# Connectors.net
KiCad netlist of a schematic drawn in Altium Designer
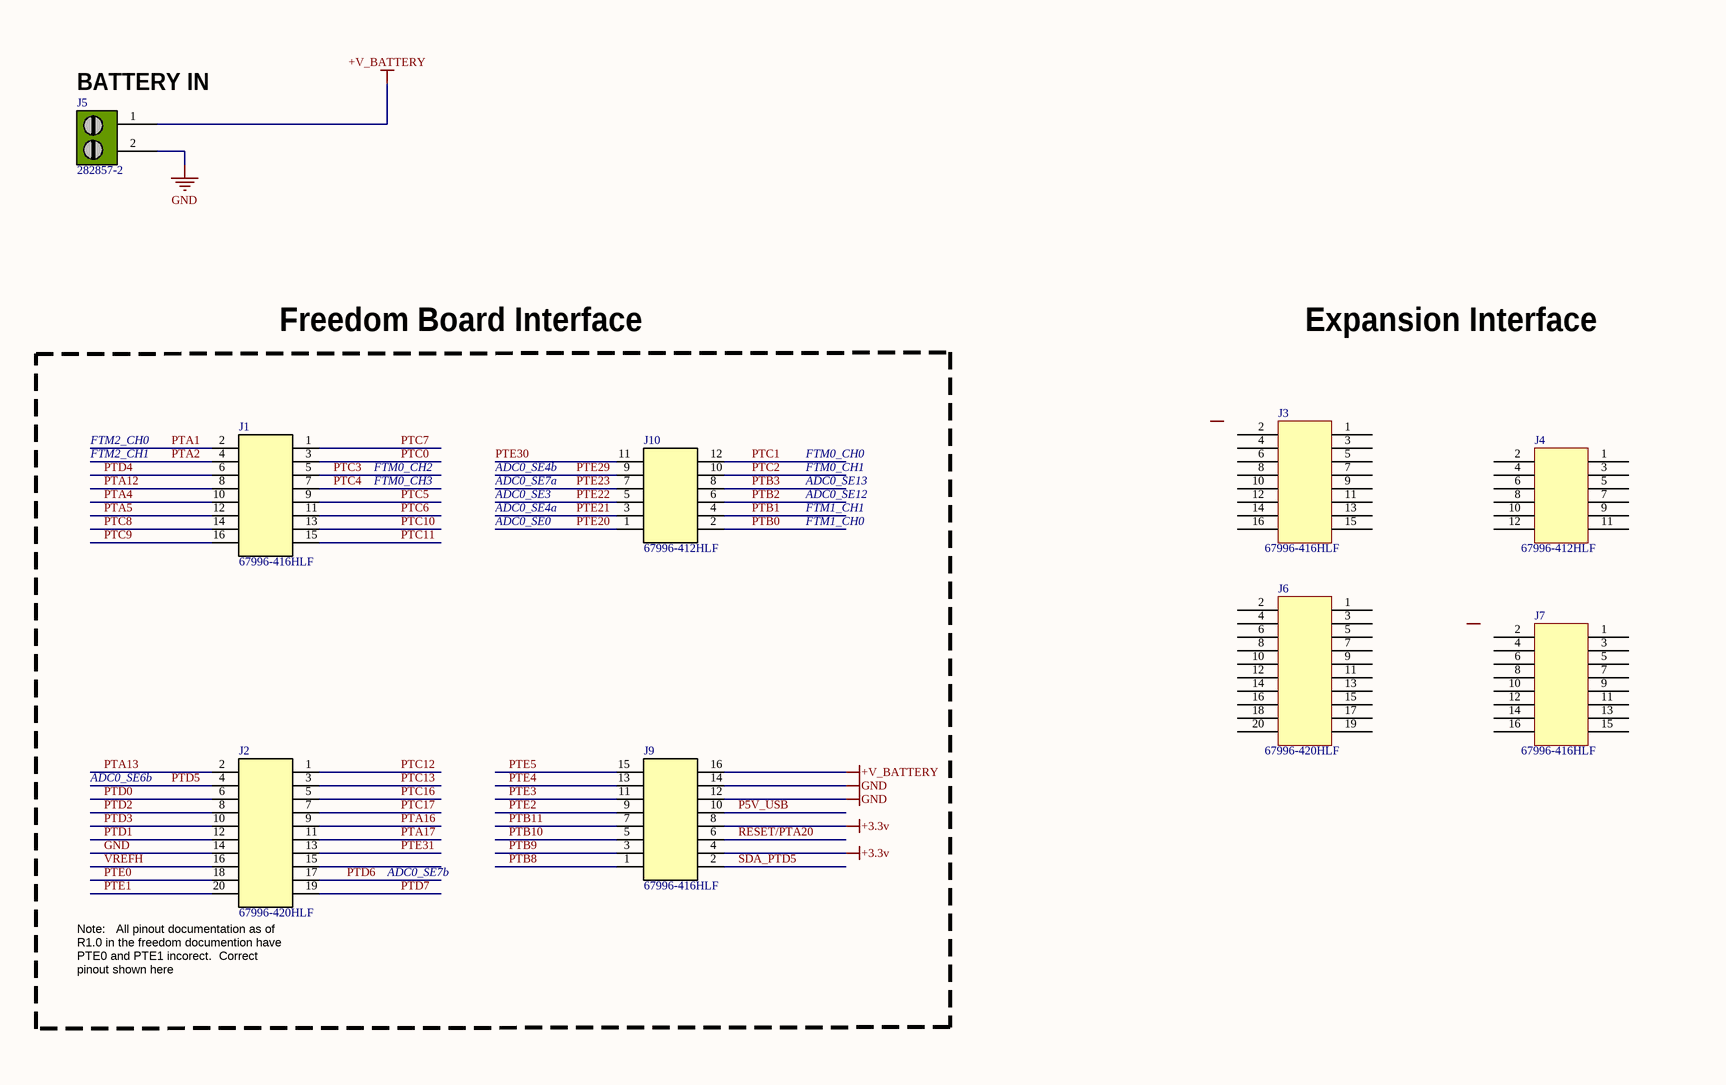
[diagram p0: Connectors.SchDoc, top left]
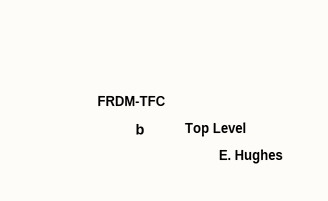
[diagram p1: Connectors.SchDoc, bottom right]

(export (version "E")
  (design (tool "Eeschema 10.0.6"))
  (components
    (comp (ref "J1")
      (value "67996-416HLF")
      (footprint "67996-416HLF")
      (description "CONN HEADER 16POS .100 STR TIN")
      (fields (field (name "MANUFACTURER") "FCI"))
      (libsource (lib "eConnector") (part "67996-416HLF"))
    )
    (comp (ref "J2")
      (value "67996-420HLF")
      (footprint "67996-420HLF")
      (description "CONN HEADER 20POS .100 STR TIN")
      (fields (field (name "MANUFACTURER") "FCI"))
      (libsource (lib "eConnector") (part "67996-420HLF"))
    )
    (comp (ref "J3")
      (value "67996-416HLF")
      (footprint "67996-416HLF")
      (description "CONN HEADER 16POS .100 STR TIN")
      (libsource (lib "Amphenol_Connectors") (part "67996-416HLF"))
    )
    (comp (ref "J4")
      (value "67996-412HLF")
      (footprint "67996-412HLF")
      (description "CONN HEADER 12POS .100 STR TIN")
      (libsource (lib "Amphenol_Connectors") (part "67996-412HLF"))
    )
    (comp (ref "J5")
      (value "282857-2")
      (footprint "282857-2")
      (description "TERM BLOCK 2POS SIDE ENT 5.08MM")
      (fields (field (name "MANUFACTURER") "TE Connectivity") (field (name "VOLTAGE") "300V"))
      (libsource (lib "eConnector") (part "282857-2"))
    )
    (comp (ref "J6")
      (value "67996-420HLF")
      (footprint "67996-420HLF")
      (description "CONN HEADER 20POS .100 STR TIN")
      (libsource (lib "Amphenol_Connectors") (part "67996-420HLF"))
    )
    (comp (ref "J7")
      (value "67996-416HLF")
      (footprint "67996-416HLF")
      (description "CONN HEADER 16POS .100 STR TIN")
      (libsource (lib "Amphenol_Connectors") (part "67996-416HLF"))
    )
    (comp (ref "J9")
      (value "67996-416HLF")
      (footprint "67996-416HLF")
      (description "CONN HEADER 16POS .100 STR TIN")
      (fields (field (name "MANUFACTURER") "FCI"))
      (libsource (lib "") (part "67996-416HLF_1"))
    )
    (comp (ref "J10")
      (value "67996-412HLF")
      (footprint "67996-412HLF")
      (description "CONN HEADER 12POS .100 STR TIN")
      (fields (field (name "MANUFACTURER") "FCI"))
      (libsource (lib "eConnector") (part "67996-412HLF"))
    )
  )
  (nets
    (net (code "1") (name "+3.3v") (class "Default")
      (node (ref "J9") (pin "4") (pinfunction "4_4") (pintype "passive"))
      (node (ref "J9") (pin "8") (pinfunction "8_8") (pintype "passive"))
    )
    (net (code "2") (name "+V_BATTERY") (class "Default")
      (node (ref "J5") (pin "1") (pinfunction "1_1") (pintype "passive"))
      (node (ref "J9") (pin "16") (pinfunction "16_16") (pintype "passive"))
    )
    (net (code "3") (name "/P5V_USB") (class "Default")
      (node (ref "J9") (pin "10") (pinfunction "10_10") (pintype "passive"))
    )
    (net (code "4") (name "/PTA1") (class "Default")
      (node (ref "J1") (pin "2") (pinfunction "2_2") (pintype "passive"))
    )
    (net (code "5") (name "/PTA2") (class "Default")
      (node (ref "J1") (pin "4") (pinfunction "4_4") (pintype "passive"))
    )
    (net (code "6") (name "/PTA4") (class "Default")
      (node (ref "J1") (pin "10") (pinfunction "10_10") (pintype "passive"))
    )
    (net (code "7") (name "/PTA5") (class "Default")
      (node (ref "J1") (pin "12") (pinfunction "12_12") (pintype "passive"))
    )
    (net (code "8") (name "/PTA12") (class "Default")
      (node (ref "J1") (pin "8") (pinfunction "8_8") (pintype "passive"))
    )
    (net (code "9") (name "/PTA13") (class "Default")
      (node (ref "J2") (pin "2") (pinfunction "2_2") (pintype "passive"))
    )
    (net (code "10") (name "/PTA16") (class "Default")
      (node (ref "J2") (pin "9") (pinfunction "9_9") (pintype "passive"))
    )
    (net (code "11") (name "/PTA17") (class "Default")
      (node (ref "J2") (pin "11") (pinfunction "11_11") (pintype "passive"))
    )
    (net (code "12") (name "/PTB0") (class "Default")
      (node (ref "J10") (pin "2") (pinfunction "2_2") (pintype "passive"))
    )
    (net (code "13") (name "/PTB1") (class "Default")
      (node (ref "J10") (pin "4") (pinfunction "4_4") (pintype "passive"))
    )
    (net (code "14") (name "/PTB2") (class "Default")
      (node (ref "J10") (pin "6") (pinfunction "6_6") (pintype "passive"))
    )
    (net (code "15") (name "/PTB3") (class "Default")
      (node (ref "J10") (pin "8") (pinfunction "8_8") (pintype "passive"))
    )
    (net (code "16") (name "/PTB8") (class "Default")
      (node (ref "J9") (pin "1") (pinfunction "1_1") (pintype "passive"))
    )
    (net (code "17") (name "/PTB9") (class "Default")
      (node (ref "J9") (pin "3") (pinfunction "3_3") (pintype "passive"))
    )
    (net (code "18") (name "/PTB10") (class "Default")
      (node (ref "J9") (pin "5") (pinfunction "5_5") (pintype "passive"))
    )
    (net (code "19") (name "/PTB11") (class "Default")
      (node (ref "J9") (pin "7") (pinfunction "7_7") (pintype "passive"))
    )
    (net (code "20") (name "/PTC0") (class "Default")
      (node (ref "J1") (pin "3") (pinfunction "3_3") (pintype "passive"))
    )
    (net (code "21") (name "/PTC1") (class "Default")
      (node (ref "J10") (pin "12") (pinfunction "12_12") (pintype "passive"))
    )
    (net (code "22") (name "/PTC2") (class "Default")
      (node (ref "J10") (pin "10") (pinfunction "10_10") (pintype "passive"))
    )
    (net (code "23") (name "/PTC3") (class "Default")
      (node (ref "J1") (pin "5") (pinfunction "5_5") (pintype "passive"))
    )
    (net (code "24") (name "/PTC4") (class "Default")
      (node (ref "J1") (pin "7") (pinfunction "7_7") (pintype "passive"))
    )
    (net (code "25") (name "/PTC5") (class "Default")
      (node (ref "J1") (pin "9") (pinfunction "9_9") (pintype "passive"))
    )
    (net (code "26") (name "/PTC6") (class "Default")
      (node (ref "J1") (pin "11") (pinfunction "11_11") (pintype "passive"))
    )
    (net (code "27") (name "/PTC7") (class "Default")
      (node (ref "J1") (pin "1") (pinfunction "1_1") (pintype "passive"))
    )
    (net (code "28") (name "/PTC8") (class "Default")
      (node (ref "J1") (pin "14") (pinfunction "14_14") (pintype "passive"))
    )
    (net (code "29") (name "/PTC9") (class "Default")
      (node (ref "J1") (pin "16") (pinfunction "16_16") (pintype "passive"))
    )
    (net (code "30") (name "/PTC10") (class "Default")
      (node (ref "J1") (pin "13") (pinfunction "13_13") (pintype "passive"))
    )
    (net (code "31") (name "/PTC11") (class "Default")
      (node (ref "J1") (pin "15") (pinfunction "15_15") (pintype "passive"))
    )
    (net (code "32") (name "/PTC12") (class "Default")
      (node (ref "J2") (pin "1") (pinfunction "1_1") (pintype "passive"))
    )
    (net (code "33") (name "/PTC13") (class "Default")
      (node (ref "J2") (pin "3") (pinfunction "3_3") (pintype "passive"))
    )
    (net (code "34") (name "/PTC16") (class "Default")
      (node (ref "J2") (pin "5") (pinfunction "5_5") (pintype "passive"))
    )
    (net (code "35") (name "/PTC17") (class "Default")
      (node (ref "J2") (pin "7") (pinfunction "7_7") (pintype "passive"))
    )
    (net (code "36") (name "/PTD0") (class "Default")
      (node (ref "J2") (pin "6") (pinfunction "6_6") (pintype "passive"))
    )
    (net (code "37") (name "/PTD1") (class "Default")
      (node (ref "J2") (pin "12") (pinfunction "12_12") (pintype "passive"))
    )
    (net (code "38") (name "/PTD2") (class "Default")
      (node (ref "J2") (pin "8") (pinfunction "8_8") (pintype "passive"))
    )
    (net (code "39") (name "/PTD3") (class "Default")
      (node (ref "J2") (pin "10") (pinfunction "10_10") (pintype "passive"))
    )
    (net (code "40") (name "/PTD4") (class "Default")
      (node (ref "J1") (pin "6") (pinfunction "6_6") (pintype "passive"))
    )
    (net (code "41") (name "/PTD5") (class "Default")
      (node (ref "J2") (pin "4") (pinfunction "4_4") (pintype "passive"))
    )
    (net (code "42") (name "/PTD6") (class "Default")
      (node (ref "J2") (pin "17") (pinfunction "17_17") (pintype "passive"))
    )
    (net (code "43") (name "/PTD7") (class "Default")
      (node (ref "J2") (pin "19") (pinfunction "19_19") (pintype "passive"))
    )
    (net (code "44") (name "/PTE0") (class "Default")
      (node (ref "J2") (pin "18") (pinfunction "18_18") (pintype "passive"))
    )
    (net (code "45") (name "/PTE1") (class "Default")
      (node (ref "J2") (pin "20") (pinfunction "20_20") (pintype "passive"))
    )
    (net (code "46") (name "/PTE2") (class "Default")
      (node (ref "J9") (pin "9") (pinfunction "9_9") (pintype "passive"))
    )
    (net (code "47") (name "/PTE3") (class "Default")
      (node (ref "J9") (pin "11") (pinfunction "11_11") (pintype "passive"))
    )
    (net (code "48") (name "/PTE4") (class "Default")
      (node (ref "J9") (pin "13") (pinfunction "13_13") (pintype "passive"))
    )
    (net (code "49") (name "/PTE5") (class "Default")
      (node (ref "J9") (pin "15") (pinfunction "15_15") (pintype "passive"))
    )
    (net (code "50") (name "/PTE20") (class "Default")
      (node (ref "J10") (pin "1") (pinfunction "1_1") (pintype "passive"))
    )
    (net (code "51") (name "/PTE21") (class "Default")
      (node (ref "J10") (pin "3") (pinfunction "3_3") (pintype "passive"))
    )
    (net (code "52") (name "/PTE22") (class "Default")
      (node (ref "J10") (pin "5") (pinfunction "5_5") (pintype "passive"))
    )
    (net (code "53") (name "/PTE23") (class "Default")
      (node (ref "J10") (pin "7") (pinfunction "7_7") (pintype "passive"))
    )
    (net (code "54") (name "/PTE29") (class "Default")
      (node (ref "J10") (pin "9") (pinfunction "9_9") (pintype "passive"))
    )
    (net (code "55") (name "/PTE30") (class "Default")
      (node (ref "J10") (pin "11") (pinfunction "11_11") (pintype "passive"))
    )
    (net (code "56") (name "/PTE31") (class "Default")
      (node (ref "J2") (pin "13") (pinfunction "13_13") (pintype "passive"))
    )
    (net (code "57") (name "/RESET{slash}PTA20") (class "Default")
      (node (ref "J9") (pin "6") (pinfunction "6_6") (pintype "passive"))
    )
    (net (code "58") (name "/SDA_PTD5") (class "Default")
      (node (ref "J9") (pin "2") (pinfunction "2_2") (pintype "passive"))
    )
    (net (code "59") (name "/VREFH") (class "Default")
      (node (ref "J2") (pin "16") (pinfunction "16_16") (pintype "passive"))
    )
    (net (code "60") (name "GND") (class "Default")
      (node (ref "J2") (pin "14") (pinfunction "14_14") (pintype "passive"))
      (node (ref "J5") (pin "2") (pinfunction "2_2") (pintype "passive"))
      (node (ref "J9") (pin "12") (pinfunction "12_12") (pintype "passive"))
      (node (ref "J9") (pin "14") (pinfunction "14_14") (pintype "passive"))
    )
    (net (code "61") (name "unconnected-(J2-Pad15)") (class "Default")
      (node (ref "J2") (pin "15") (pinfunction "15_15") (pintype "passive"))
    )
    (net (code "62") (name "unconnected-(J3-Pad1)") (class "Default")
      (node (ref "J3") (pin "1") (pinfunction "1_1") (pintype "passive"))
    )
    (net (code "63") (name "unconnected-(J3-Pad2)") (class "Default")
      (node (ref "J3") (pin "2") (pinfunction "2_2") (pintype "passive"))
    )
    (net (code "64") (name "unconnected-(J3-Pad3)") (class "Default")
      (node (ref "J3") (pin "3") (pinfunction "3_3") (pintype "passive"))
    )
    (net (code "65") (name "unconnected-(J3-Pad4)") (class "Default")
      (node (ref "J3") (pin "4") (pinfunction "4_4") (pintype "passive"))
    )
    (net (code "66") (name "unconnected-(J3-Pad5)") (class "Default")
      (node (ref "J3") (pin "5") (pinfunction "5_5") (pintype "passive"))
    )
    (net (code "67") (name "unconnected-(J3-Pad6)") (class "Default")
      (node (ref "J3") (pin "6") (pinfunction "6_6") (pintype "passive"))
    )
    (net (code "68") (name "unconnected-(J3-Pad7)") (class "Default")
      (node (ref "J3") (pin "7") (pinfunction "7_7") (pintype "passive"))
    )
    (net (code "69") (name "unconnected-(J3-Pad8)") (class "Default")
      (node (ref "J3") (pin "8") (pinfunction "8_8") (pintype "passive"))
    )
    (net (code "70") (name "unconnected-(J3-Pad9)") (class "Default")
      (node (ref "J3") (pin "9") (pinfunction "9_9") (pintype "passive"))
    )
    (net (code "71") (name "unconnected-(J3-Pad10)") (class "Default")
      (node (ref "J3") (pin "10") (pinfunction "10_10") (pintype "passive"))
    )
    (net (code "72") (name "unconnected-(J3-Pad11)") (class "Default")
      (node (ref "J3") (pin "11") (pinfunction "11_11") (pintype "passive"))
    )
    (net (code "73") (name "unconnected-(J3-Pad12)") (class "Default")
      (node (ref "J3") (pin "12") (pinfunction "12_12") (pintype "passive"))
    )
    (net (code "74") (name "unconnected-(J3-Pad13)") (class "Default")
      (node (ref "J3") (pin "13") (pinfunction "13_13") (pintype "passive"))
    )
    (net (code "75") (name "unconnected-(J3-Pad14)") (class "Default")
      (node (ref "J3") (pin "14") (pinfunction "14_14") (pintype "passive"))
    )
    (net (code "76") (name "unconnected-(J3-Pad15)") (class "Default")
      (node (ref "J3") (pin "15") (pinfunction "15_15") (pintype "passive"))
    )
    (net (code "77") (name "unconnected-(J3-Pad16)") (class "Default")
      (node (ref "J3") (pin "16") (pinfunction "16_16") (pintype "passive"))
    )
    (net (code "78") (name "unconnected-(J4-Pad1)") (class "Default")
      (node (ref "J4") (pin "1") (pinfunction "1_1") (pintype "passive"))
    )
    (net (code "79") (name "unconnected-(J4-Pad2)") (class "Default")
      (node (ref "J4") (pin "2") (pinfunction "2_2") (pintype "passive"))
    )
    (net (code "80") (name "unconnected-(J4-Pad3)") (class "Default")
      (node (ref "J4") (pin "3") (pinfunction "3_3") (pintype "passive"))
    )
    (net (code "81") (name "unconnected-(J4-Pad4)") (class "Default")
      (node (ref "J4") (pin "4") (pinfunction "4_4") (pintype "passive"))
    )
    (net (code "82") (name "unconnected-(J4-Pad5)") (class "Default")
      (node (ref "J4") (pin "5") (pinfunction "5_5") (pintype "passive"))
    )
    (net (code "83") (name "unconnected-(J4-Pad6)") (class "Default")
      (node (ref "J4") (pin "6") (pinfunction "6_6") (pintype "passive"))
    )
    (net (code "84") (name "unconnected-(J4-Pad7)") (class "Default")
      (node (ref "J4") (pin "7") (pinfunction "7_7") (pintype "passive"))
    )
    (net (code "85") (name "unconnected-(J4-Pad8)") (class "Default")
      (node (ref "J4") (pin "8") (pinfunction "8_8") (pintype "passive"))
    )
    (net (code "86") (name "unconnected-(J4-Pad9)") (class "Default")
      (node (ref "J4") (pin "9") (pinfunction "9_9") (pintype "passive"))
    )
    (net (code "87") (name "unconnected-(J4-Pad10)") (class "Default")
      (node (ref "J4") (pin "10") (pinfunction "10_10") (pintype "passive"))
    )
    (net (code "88") (name "unconnected-(J4-Pad11)") (class "Default")
      (node (ref "J4") (pin "11") (pinfunction "11_11") (pintype "passive"))
    )
    (net (code "89") (name "unconnected-(J4-Pad12)") (class "Default")
      (node (ref "J4") (pin "12") (pinfunction "12_12") (pintype "passive"))
    )
    (net (code "90") (name "unconnected-(J6-Pad1)") (class "Default")
      (node (ref "J6") (pin "1") (pinfunction "1_1") (pintype "passive"))
    )
    (net (code "91") (name "unconnected-(J6-Pad2)") (class "Default")
      (node (ref "J6") (pin "2") (pinfunction "2_2") (pintype "passive"))
    )
    (net (code "92") (name "unconnected-(J6-Pad3)") (class "Default")
      (node (ref "J6") (pin "3") (pinfunction "3_3") (pintype "passive"))
    )
    (net (code "93") (name "unconnected-(J6-Pad4)") (class "Default")
      (node (ref "J6") (pin "4") (pinfunction "4_4") (pintype "passive"))
    )
    (net (code "94") (name "unconnected-(J6-Pad5)") (class "Default")
      (node (ref "J6") (pin "5") (pinfunction "5_5") (pintype "passive"))
    )
    (net (code "95") (name "unconnected-(J6-Pad6)") (class "Default")
      (node (ref "J6") (pin "6") (pinfunction "6_6") (pintype "passive"))
    )
    (net (code "96") (name "unconnected-(J6-Pad7)") (class "Default")
      (node (ref "J6") (pin "7") (pinfunction "7_7") (pintype "passive"))
    )
    (net (code "97") (name "unconnected-(J6-Pad8)") (class "Default")
      (node (ref "J6") (pin "8") (pinfunction "8_8") (pintype "passive"))
    )
    (net (code "98") (name "unconnected-(J6-Pad9)") (class "Default")
      (node (ref "J6") (pin "9") (pinfunction "9_9") (pintype "passive"))
    )
    (net (code "99") (name "unconnected-(J6-Pad10)") (class "Default")
      (node (ref "J6") (pin "10") (pinfunction "10_10") (pintype "passive"))
    )
    (net (code "100") (name "unconnected-(J6-Pad11)") (class "Default")
      (node (ref "J6") (pin "11") (pinfunction "11_11") (pintype "passive"))
    )
    (net (code "101") (name "unconnected-(J6-Pad12)") (class "Default")
      (node (ref "J6") (pin "12") (pinfunction "12_12") (pintype "passive"))
    )
    (net (code "102") (name "unconnected-(J6-Pad13)") (class "Default")
      (node (ref "J6") (pin "13") (pinfunction "13_13") (pintype "passive"))
    )
    (net (code "103") (name "unconnected-(J6-Pad14)") (class "Default")
      (node (ref "J6") (pin "14") (pinfunction "14_14") (pintype "passive"))
    )
    (net (code "104") (name "unconnected-(J6-Pad15)") (class "Default")
      (node (ref "J6") (pin "15") (pinfunction "15_15") (pintype "passive"))
    )
    (net (code "105") (name "unconnected-(J6-Pad16)") (class "Default")
      (node (ref "J6") (pin "16") (pinfunction "16_16") (pintype "passive"))
    )
    (net (code "106") (name "unconnected-(J6-Pad17)") (class "Default")
      (node (ref "J6") (pin "17") (pinfunction "17_17") (pintype "passive"))
    )
    (net (code "107") (name "unconnected-(J6-Pad18)") (class "Default")
      (node (ref "J6") (pin "18") (pinfunction "18_18") (pintype "passive"))
    )
    (net (code "108") (name "unconnected-(J6-Pad19)") (class "Default")
      (node (ref "J6") (pin "19") (pinfunction "19_19") (pintype "passive"))
    )
    (net (code "109") (name "unconnected-(J6-Pad20)") (class "Default")
      (node (ref "J6") (pin "20") (pinfunction "20_20") (pintype "passive"))
    )
    (net (code "110") (name "unconnected-(J7-Pad1)") (class "Default")
      (node (ref "J7") (pin "1") (pinfunction "1_1") (pintype "passive"))
    )
    (net (code "111") (name "unconnected-(J7-Pad2)") (class "Default")
      (node (ref "J7") (pin "2") (pinfunction "2_2") (pintype "passive"))
    )
    (net (code "112") (name "unconnected-(J7-Pad3)") (class "Default")
      (node (ref "J7") (pin "3") (pinfunction "3_3") (pintype "passive"))
    )
    (net (code "113") (name "unconnected-(J7-Pad4)") (class "Default")
      (node (ref "J7") (pin "4") (pinfunction "4_4") (pintype "passive"))
    )
    (net (code "114") (name "unconnected-(J7-Pad5)") (class "Default")
      (node (ref "J7") (pin "5") (pinfunction "5_5") (pintype "passive"))
    )
    (net (code "115") (name "unconnected-(J7-Pad6)") (class "Default")
      (node (ref "J7") (pin "6") (pinfunction "6_6") (pintype "passive"))
    )
    (net (code "116") (name "unconnected-(J7-Pad7)") (class "Default")
      (node (ref "J7") (pin "7") (pinfunction "7_7") (pintype "passive"))
    )
    (net (code "117") (name "unconnected-(J7-Pad8)") (class "Default")
      (node (ref "J7") (pin "8") (pinfunction "8_8") (pintype "passive"))
    )
    (net (code "118") (name "unconnected-(J7-Pad9)") (class "Default")
      (node (ref "J7") (pin "9") (pinfunction "9_9") (pintype "passive"))
    )
    (net (code "119") (name "unconnected-(J7-Pad10)") (class "Default")
      (node (ref "J7") (pin "10") (pinfunction "10_10") (pintype "passive"))
    )
    (net (code "120") (name "unconnected-(J7-Pad11)") (class "Default")
      (node (ref "J7") (pin "11") (pinfunction "11_11") (pintype "passive"))
    )
    (net (code "121") (name "unconnected-(J7-Pad12)") (class "Default")
      (node (ref "J7") (pin "12") (pinfunction "12_12") (pintype "passive"))
    )
    (net (code "122") (name "unconnected-(J7-Pad13)") (class "Default")
      (node (ref "J7") (pin "13") (pinfunction "13_13") (pintype "passive"))
    )
    (net (code "123") (name "unconnected-(J7-Pad14)") (class "Default")
      (node (ref "J7") (pin "14") (pinfunction "14_14") (pintype "passive"))
    )
    (net (code "124") (name "unconnected-(J7-Pad15)") (class "Default")
      (node (ref "J7") (pin "15") (pinfunction "15_15") (pintype "passive"))
    )
    (net (code "125") (name "unconnected-(J7-Pad16)") (class "Default")
      (node (ref "J7") (pin "16") (pinfunction "16_16") (pintype "passive"))
    )
  )
)
